# Sheet2.net
KiCad netlist of a schematic drawn in Altium Designer
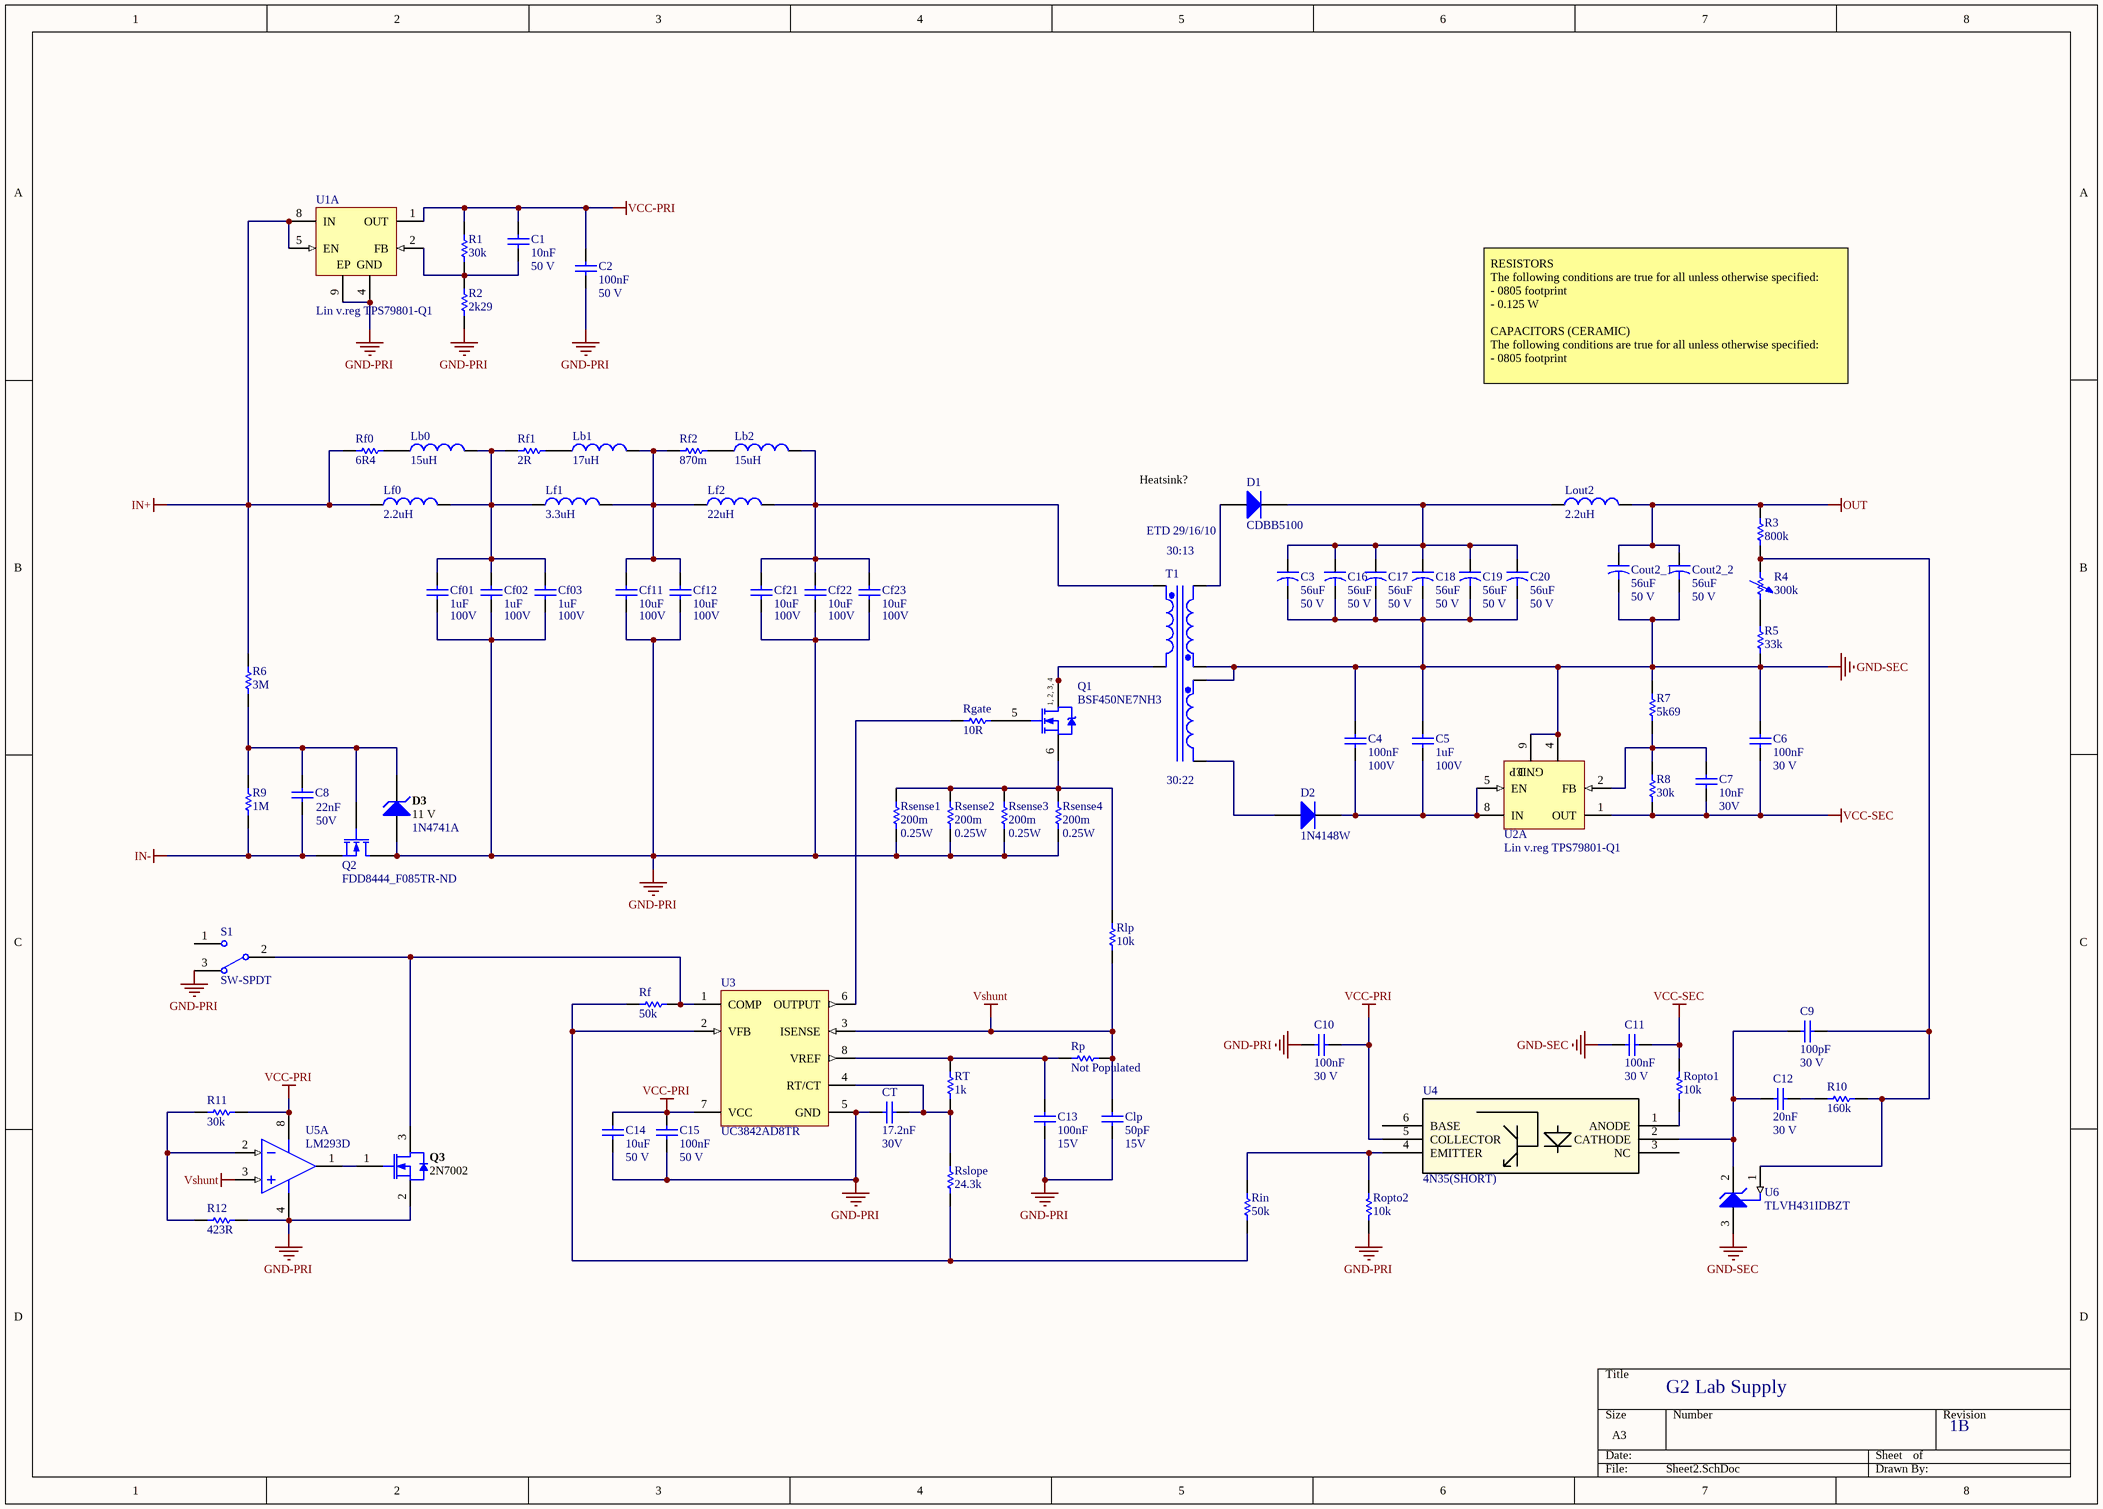
[diagram p0: Sheet2.SchDoc]

(export (version "E")
  (design (tool "Eeschema 10.0.6"))
  (components
    (comp (ref "C1")
      (value "10nF")
      (footprint "CAPC0805(2012)145_N")
      (description "CAP 82nF")
      (fields (field (name "RATED VOLTAGE") "50 V") (field (name "TOLERANCE") "Â±10%"))
      (libsource (lib "Altium Content Vault") (part "CMP-1036-04379-1"))
    )
    (comp (ref "C2")
      (value "100nF")
      (footprint "CAPC0805(2012)145_N")
      (description "CAP 82nF")
      (fields (field (name "RATED VOLTAGE") "50 V") (field (name "TOLERANCE") "Â±10%"))
      (libsource (lib "Altium Content Vault") (part "CMP-1036-04379-1"))
    )
    (comp (ref "C3")
      (value "56uF")
      (footprint "CAPR5-4X5")
      (description "Capacitor")
      (fields
        (field (name "VOLTAGE - RATED") "50 V")
        (field (name "Comment") "Cap2")
        (field (name "PUBLISHER") "Altium Limited")
      )
      (libsource (lib "Miscellaneous Devices") (part "Cap2"))
    )
    (comp (ref "C4")
      (value "100nF")
      (footprint "CAPC0805(2012)145_N")
      (description "footprint not correct")
      (fields (field (name "RATED VOLTAGE") "100V") (field (name "TOLERANCE") "Â±10%"))
      (libsource (lib "Altium Content Vault") (part "CMP-1036-04379-1"))
    )
    (comp (ref "C5")
      (value "1uF")
      (footprint "CAPC3216X180X20LL20")
      (description "Chip Capacitor, 1 uF, +/- 10%, 100 V, -55 to 125 degC, 1206 (3216 Metric), RoHS, Tape and Reel")
      (fields
        (field (name "MANUFACTURER") "TDK")
        (field (name "VOLTAGE - RATED") "100V")
        (field (name "TOLERANCE") "±10%")
      )
      (libsource (lib "Altium Content Vault") (part "CMP-2000-06049-1"))
    )
    (comp (ref "C6")
      (value "100nF")
      (footprint "CAPC0805(2012)145_N")
      (description "CAP 82nF")
      (fields (field (name "RATED VOLTAGE") "30 V") (field (name "TOLERANCE") "Â±10%"))
      (libsource (lib "Altium Content Vault") (part "CMP-1036-04379-1"))
    )
    (comp (ref "C7")
      (value "10nF")
      (footprint "CAPC0805(2012)145_N")
      (description "CAP 82nF")
      (fields (field (name "RATED VOLTAGE") "30V") (field (name "TOLERANCE") "Â±10%"))
      (libsource (lib "Altium Content Vault") (part "CMP-1036-04379-1"))
    )
    (comp (ref "C8")
      (value "22nF")
      (footprint "CAPC0805(2012)145_N")
      (description "CAP 82nF")
      (fields (field (name "RATED VOLTAGE") "50V") (field (name "TOLERANCE") "Â±10%"))
      (libsource (lib "Altium Content Vault") (part "CMP-1036-04379-1"))
    )
    (comp (ref "C9")
      (value "100pF")
      (footprint "CAPC0805(2012)145_N")
      (description "CAP 82nF")
      (fields (field (name "RATED VOLTAGE") "30 V") (field (name "TOLERANCE") "Â±10%"))
      (libsource (lib "Altium Content Vault") (part "CMP-1036-04379-1"))
    )
    (comp (ref "C10")
      (value "100nF")
      (footprint "CAPC0805(2012)145_N")
      (description "CAP 82nF")
      (fields (field (name "RATED VOLTAGE") "30 V") (field (name "TOLERANCE") "Â±10%"))
      (libsource (lib "Altium Content Vault") (part "CMP-1036-04379-1"))
    )
    (comp (ref "C11")
      (value "100nF")
      (footprint "CAPC0805(2012)145_N")
      (description "CAP 82nF")
      (fields (field (name "RATED VOLTAGE") "30 V") (field (name "TOLERANCE") "Â±10%"))
      (libsource (lib "Altium Content Vault") (part "CMP-1036-04379-1"))
    )
    (comp (ref "C12")
      (value "20nF")
      (footprint "CAPC0805(2012)145_N")
      (description "CAP 82nF")
      (fields (field (name "RATED VOLTAGE") "30 V") (field (name "TOLERANCE") "Â±10%"))
      (libsource (lib "Altium Content Vault") (part "CMP-1036-04379-1"))
    )
    (comp (ref "C13")
      (value "100nF")
      (footprint "CAPC0805(2012)145_N")
      (description "CAP 82nF")
      (fields (field (name "RATED VOLTAGE") "15V") (field (name "TOLERANCE") "Â±10%"))
      (libsource (lib "Altium Content Vault") (part "CMP-1036-04379-1"))
    )
    (comp (ref "C14")
      (value "10uF")
      (footprint "CAPC0805(2012)145_N")
      (description "CAP 82nF")
      (fields (field (name "RATED VOLTAGE") "50 V") (field (name "TOLERANCE") "Â±10%"))
      (libsource (lib "Altium Content Vault") (part "CMP-1036-04379-1"))
    )
    (comp (ref "C15")
      (value "100nF")
      (footprint "CAPC0805(2012)145_N")
      (description "CAP 82nF")
      (fields (field (name "RATED VOLTAGE") "50 V") (field (name "TOLERANCE") "Â±10%"))
      (libsource (lib "Altium Content Vault") (part "CMP-1036-04379-1"))
    )
    (comp (ref "C16")
      (value "56uF")
      (footprint "CAPR5-4X5")
      (description "Capacitor")
      (fields
        (field (name "VOLTAGE - RATED") "50 V")
        (field (name "Comment") "Cap2")
        (field (name "PUBLISHER") "Altium Limited")
      )
      (libsource (lib "Miscellaneous Devices") (part "Cap2"))
    )
    (comp (ref "C17")
      (value "56uF")
      (footprint "CAPR5-4X5")
      (description "Capacitor")
      (fields
        (field (name "VOLTAGE - RATED") "50 V")
        (field (name "Comment") "Cap2")
        (field (name "PUBLISHER") "Altium Limited")
      )
      (libsource (lib "Miscellaneous Devices") (part "Cap2"))
    )
    (comp (ref "C18")
      (value "56uF")
      (footprint "CAPR5-4X5")
      (description "Capacitor")
      (fields
        (field (name "VOLTAGE - RATED") "50 V")
        (field (name "Comment") "Cap2")
        (field (name "PUBLISHER") "Altium Limited")
      )
      (libsource (lib "Miscellaneous Devices") (part "Cap2"))
    )
    (comp (ref "C19")
      (value "56uF")
      (footprint "CAPR5-4X5")
      (description "Capacitor")
      (fields
        (field (name "VOLTAGE - RATED") "50 V")
        (field (name "Comment") "Cap2")
        (field (name "PUBLISHER") "Altium Limited")
      )
      (libsource (lib "Miscellaneous Devices") (part "Cap2"))
    )
    (comp (ref "C20")
      (value "56uF")
      (footprint "CAPR5-4X5")
      (description "Capacitor")
      (fields
        (field (name "VOLTAGE - RATED") "50 V")
        (field (name "Comment") "Cap2")
        (field (name "PUBLISHER") "Altium Limited")
      )
      (libsource (lib "Miscellaneous Devices") (part "Cap2"))
    )
    (comp (ref "Cf01")
      (value "1uF")
      (footprint "CAPC3216X180X20LL20")
      (description "Chip Capacitor, 1 uF, +/- 10%, 100 V, -55 to 125 degC, 1206 (3216 Metric), RoHS, Tape and Reel")
      (fields
        (field (name "MANUFACTURER") "TDK")
        (field (name "VOLTAGE - RATED") "100V")
        (field (name "TOLERANCE") "±10%")
      )
      (libsource (lib "Altium Content Vault") (part "CMP-2000-06049-1"))
    )
    (comp (ref "Cf02")
      (value "1uF")
      (footprint "CAPC3216X180X20LL20")
      (description "Chip Capacitor, 1 uF, +/- 10%, 100 V, -55 to 125 degC, 1206 (3216 Metric), RoHS, Tape and Reel")
      (fields
        (field (name "MANUFACTURER") "TDK")
        (field (name "VOLTAGE - RATED") "100V")
        (field (name "TOLERANCE") "±10%")
      )
      (libsource (lib "Altium Content Vault") (part "CMP-2000-06049-1"))
    )
    (comp (ref "Cf03")
      (value "1uF")
      (footprint "CAPC3216X180X20LL20")
      (description "Chip Capacitor, 1 uF, +/- 10%, 100 V, -55 to 125 degC, 1206 (3216 Metric), RoHS, Tape and Reel")
      (fields
        (field (name "MANUFACTURER") "TDK")
        (field (name "VOLTAGE - RATED") "100V")
        (field (name "TOLERANCE") "±10%")
      )
      (libsource (lib "Altium Content Vault") (part "CMP-2000-06049-1"))
    )
    (comp (ref "Cf11")
      (value "10uF")
      (footprint "CAPC5750X250X20LL40")
      (description "Chip Capacitor, 10 uF, +/- 10%, 100 V, -55 to 125 degC, 2220 (5750 Metric), RoHS, Tape and Reel")
      (fields (field (name "MANUFACTURER") "TDK") (field (name "VOLTAGE - RATED") "100V"))
      (libsource (lib "Altium Content Vault") (part "CMP-2000-07445-1"))
    )
    (comp (ref "Cf12")
      (value "10uF")
      (footprint "CAPC5750X250X20LL40")
      (description "Chip Capacitor, 10 uF, +/- 10%, 100 V, -55 to 125 degC, 2220 (5750 Metric), RoHS, Tape and Reel")
      (fields (field (name "MANUFACTURER") "TDK") (field (name "VOLTAGE - RATED") "100V"))
      (libsource (lib "Altium Content Vault") (part "CMP-2000-07445-1"))
    )
    (comp (ref "Cf21")
      (value "10uF")
      (footprint "CAPC5750X250X20LL40")
      (description "Chip Capacitor, 10 uF, +/- 10%, 100 V, -55 to 125 degC, 2220 (5750 Metric), RoHS, Tape and Reel")
      (fields (field (name "MANUFACTURER") "TDK") (field (name "VOLTAGE - RATED") "100V"))
      (libsource (lib "Altium Content Vault") (part "CMP-2000-07445-1"))
    )
    (comp (ref "Cf22")
      (value "10uF")
      (footprint "CAPC5750X250X20LL40")
      (description "Chip Capacitor, 10 uF, +/- 10%, 100 V, -55 to 125 degC, 2220 (5750 Metric), RoHS, Tape and Reel")
      (fields (field (name "MANUFACTURER") "TDK") (field (name "VOLTAGE - RATED") "100V"))
      (libsource (lib "Altium Content Vault") (part "CMP-2000-07445-1"))
    )
    (comp (ref "Cf23")
      (value "10uF")
      (footprint "CAPC5750X250X20LL40")
      (description "Chip Capacitor, 10 uF, +/- 10%, 100 V, -55 to 125 degC, 2220 (5750 Metric), RoHS, Tape and Reel")
      (fields (field (name "MANUFACTURER") "TDK") (field (name "VOLTAGE - RATED") "100V"))
      (libsource (lib "Altium Content Vault") (part "CMP-2000-07445-1"))
    )
    (comp (ref "Clp")
      (value "50pF")
      (footprint "CAPC0805(2012)145_N")
      (description "CAP 82nF")
      (fields (field (name "RATED VOLTAGE") "15V") (field (name "TOLERANCE") "Â±10%"))
      (libsource (lib "Altium Content Vault") (part "CMP-1036-04379-1"))
    )
    (comp (ref "Cout2_1")
      (value "56uF")
      (footprint "CAPR5-4X5")
      (description "Capacitor")
      (fields
        (field (name "VOLTAGE - RATED") "50 V")
        (field (name "Comment") "Cap2")
        (field (name "PUBLISHER") "Altium Limited")
      )
      (libsource (lib "Miscellaneous Devices") (part "Cap2"))
    )
    (comp (ref "Cout2_2")
      (value "56uF")
      (footprint "CAPR5-4X5")
      (description "Capacitor")
      (fields (field (name "VOLTAGE - RATED") "50 V") (field (name "PUBLISHER") "Altium Limited"))
      (libsource (lib "Miscellaneous Devices") (part "Cap2"))
    )
    (comp (ref "CT")
      (value "17.2nF")
      (footprint "CAPC0805(2012)145_N")
      (description "CAP 82nF")
      (fields (field (name "RATED VOLTAGE") "30V") (field (name "TOLERANCE") "Â±10%"))
      (libsource (lib "Altium Content Vault") (part "CMP-1036-04379-1"))
    )
    (comp (ref "D1")
      (value "CDBB5100")
      (footprint "SMC")
      (description "Default Diode")
      (fields (field (name "PUBLISHER") "Altium Limited"))
      (libsource (lib "Miscellaneous Devices") (part "Diode"))
    )
    (comp (ref "D2")
      (value "1N4148W")
      (footprint "JSCJ-SOD-123-2_V")
      (description "Fast Switching Diode, 75 V, 150 mA, 2-Pin 2.7 x 1.6 x 1.25 mm SMD, Tape and Reel")
      (fields (field (name "MANUFACTURER") "Changjiang Electronics"))
      (libsource (lib "Altium Content Vault") (part "CMP-0914-00001-1"))
    )
    (comp (ref "D3")
      (value "11 V")
      (footprint "FAIR-DO-41-2_V")
      (description "Zener Diode, 11V, 1W, 5%, -65 to 200 degC, 2-Pin DO-41, Body 2.72 x 5.2 mm, RoHS")
      (fields
        (field (name "MANUFACTURER") "Fairchild Semiconductor")
        (field (name "PARTNUMBER") "1N4741A")
        (field (name "TOLERANCE") "5%")
      )
      (libsource (lib "Altium Content Vault") (part "CMP-0892-00002-1"))
    )
    (comp (ref "Lb0")
      (value "15uH")
      (description "Inductor")
      (fields (field (name "PUBLISHER") "Altium Limited"))
      (libsource (lib "Miscellaneous Devices") (part "Inductor"))
    )
    (comp (ref "Lb1")
      (value "17uH")
      (description "Inductor")
      (fields (field (name "PUBLISHER") "Altium Limited"))
      (libsource (lib "Miscellaneous Devices") (part "Inductor"))
    )
    (comp (ref "Lb2")
      (value "15uH")
      (description "Inductor")
      (fields (field (name "PUBLISHER") "Altium Limited"))
      (libsource (lib "Miscellaneous Devices") (part "Inductor"))
    )
    (comp (ref "Lf0")
      (value "2.2uH")
      (description "Inductor")
      (fields (field (name "PUBLISHER") "Altium Limited"))
      (libsource (lib "Miscellaneous Devices") (part "Inductor"))
    )
    (comp (ref "Lf1")
      (value "3.3uH")
      (description "Inductor")
      (fields (field (name "PUBLISHER") "Altium Limited"))
      (libsource (lib "Miscellaneous Devices") (part "Inductor"))
    )
    (comp (ref "Lf2")
      (value "22uH")
      (description "Inductor")
      (fields (field (name "PUBLISHER") "Altium Limited"))
      (libsource (lib "Miscellaneous Devices") (part "Inductor"))
    )
    (comp (ref "Lout2")
      (value "2.2uH")
      (description "Inductor")
      (fields (field (name "PUBLISHER") "Altium Limited"))
      (libsource (lib "Miscellaneous Devices") (part "Inductor"))
    )
    (comp (ref "Q1")
      (value "BSF450NE7NH3")
      (footprint "INF-MG-WDSON-2-1_V")
      (description "N-Channel OptiMOS 3 Power-MOSFET, 75 V VDS, 15 A ID, -40 to 150 degC, MG-WDSON-2-1, Reel, Green")
      (fields (field (name "MANUFACTURER") "Infineon"))
      (libsource (lib "Altium Content Vault") (part "CMP-1091-00001-1"))
    )
    (comp (ref "Q2")
      (value "FDD8444_F085TR-ND")
      (fields (field (name "PUBLISHER") "Altium Limited"))
      (libsource (lib "Miscellaneous Devices") (part "MOSFET-N"))
    )
    (comp (ref "Q3")
      (value "2N7002")
      (footprint "INF-PG-SOT23_M")
      (fields (field (name "MANUFACTURER") "Infineon"))
      (libsource (lib "Altium Content Vault") (part "INF-NDMOS-GSD-3"))
    )
    (comp (ref "R1")
      (value "30k")
      (footprint "RESC0805(2012)_L")
      (fields (field (name "TOLERANCE") "1 %") (field (name "POWER") "0.125 W"))
      (libsource (lib "Altium Content Vault") (part "CMP-1013-00736-1"))
    )
    (comp (ref "R2")
      (value "2k29")
      (footprint "RESC0805(2012)_L")
      (fields (field (name "TOLERANCE") "1 %") (field (name "POWER") "0.125 W"))
      (libsource (lib "Altium Content Vault") (part "CMP-1013-00736-1"))
    )
    (comp (ref "R3")
      (value "800k")
      (footprint "RESC0805(2012)_L")
      (fields (field (name "TOLERANCE") "1 %") (field (name "POWER") "0.125 W"))
      (libsource (lib "Altium Content Vault") (part "CMP-1013-00736-1"))
    )
    (comp (ref "R4")
      (value "300k")
      (footprint "AXIAL-0.7")
      (description "Variable Resistor")
      (fields (field (name "PUBLISHER") "Altium Limited"))
      (libsource (lib "Miscellaneous Devices") (part "Res Adj1"))
    )
    (comp (ref "R5")
      (value "33k")
      (footprint "RESC0805(2012)_L")
      (fields (field (name "TOLERANCE") "1 %") (field (name "POWER") "0.125 W"))
      (libsource (lib "Altium Content Vault") (part "CMP-1013-00736-1"))
    )
    (comp (ref "R6")
      (value "3M")
      (footprint "RESC0805(2012)_L")
      (fields (field (name "TOLERANCE") "1 %") (field (name "POWER") "0.125 W"))
      (libsource (lib "Altium Content Vault") (part "CMP-1013-00736-1"))
    )
    (comp (ref "R7")
      (value "5k69")
      (footprint "RESC0805(2012)_L")
      (fields (field (name "TOLERANCE") "1 %") (field (name "POWER") "0.125 W"))
      (libsource (lib "Altium Content Vault") (part "CMP-1013-00736-1"))
    )
    (comp (ref "R8")
      (value "30k")
      (footprint "RESC0805(2012)_L")
      (fields (field (name "TOLERANCE") "1 %") (field (name "POWER") "0.125 W"))
      (libsource (lib "Altium Content Vault") (part "CMP-1013-00736-1"))
    )
    (comp (ref "R9")
      (value "1M")
      (footprint "RESC0805(2012)_L")
      (fields (field (name "TOLERANCE") "1 %") (field (name "POWER") "0.125 W"))
      (libsource (lib "Altium Content Vault") (part "CMP-1013-00736-1"))
    )
    (comp (ref "R10")
      (value "160k")
      (footprint "RESC0805(2012)_L")
      (fields (field (name "TOLERANCE") "1 %") (field (name "POWER") "0.125 W"))
      (libsource (lib "Altium Content Vault") (part "CMP-1013-00736-1"))
    )
    (comp (ref "R11")
      (value "30k")
      (footprint "RESC0805(2012)_L")
      (fields (field (name "TOLERANCE") "1 %") (field (name "POWER") "0.125 W"))
      (libsource (lib "Altium Content Vault") (part "CMP-1013-00736-1"))
    )
    (comp (ref "R12")
      (value "423R")
      (footprint "RESC0805(2012)_L")
      (fields (field (name "TOLERANCE") "1 %") (field (name "POWER") "0.125 W"))
      (libsource (lib "Altium Content Vault") (part "CMP-1013-00736-1"))
    )
    (comp (ref "Rf")
      (value "50k")
      (footprint "RESC0805(2012)_L")
      (fields (field (name "TOLERANCE") "1 %") (field (name "POWER") "0.125 W"))
      (libsource (lib "Altium Content Vault") (part "CMP-1013-00736-1"))
    )
    (comp (ref "Rf0")
      (value "6R4")
      (footprint "RESC0805(2012)_L")
      (fields (field (name "TOLERANCE") "1 %") (field (name "POWER") "0.125 W"))
      (libsource (lib "Altium Content Vault") (part "CMP-1013-00736-1"))
    )
    (comp (ref "Rf1")
      (value "2R")
      (footprint "RESC0805(2012)_L")
      (fields (field (name "TOLERANCE") "1 %") (field (name "POWER") "0.125 W"))
      (libsource (lib "Altium Content Vault") (part "CMP-1013-00736-1"))
    )
    (comp (ref "Rf2")
      (value "870m")
      (footprint "RESC0805(2012)_L")
      (fields (field (name "TOLERANCE") "1 %") (field (name "POWER") "0.125 W"))
      (libsource (lib "Altium Content Vault") (part "CMP-1013-00736-1"))
    )
    (comp (ref "Rgate")
      (value "10R")
      (footprint "RESC0805(2012)_L")
      (fields (field (name "TOLERANCE") "1 %") (field (name "POWER") "0.125 W"))
      (libsource (lib "Altium Content Vault") (part "CMP-1013-00736-1"))
    )
    (comp (ref "Rin")
      (value "50k")
      (footprint "RESC0805(2012)_L")
      (fields (field (name "TOLERANCE") "1 %") (field (name "POWER") "0.125 W"))
      (libsource (lib "Altium Content Vault") (part "CMP-1013-00736-1"))
    )
    (comp (ref "Rlp")
      (value "10k")
      (footprint "RESC0805(2012)_L")
      (fields (field (name "TOLERANCE") "1 %") (field (name "POWER") "0.125 W"))
      (libsource (lib "Altium Content Vault") (part "CMP-1013-00736-1"))
    )
    (comp (ref "Ropto1")
      (value "10k")
      (footprint "RESC0805(2012)_L")
      (fields (field (name "TOLERANCE") "1 %") (field (name "POWER") "0.125 W"))
      (libsource (lib "Altium Content Vault") (part "CMP-1013-00736-1"))
    )
    (comp (ref "Ropto2")
      (value "10k")
      (footprint "RESC0805(2012)_L")
      (fields (field (name "TOLERANCE") "1 %") (field (name "POWER") "0.125 W"))
      (libsource (lib "Altium Content Vault") (part "CMP-1013-00736-1"))
    )
    (comp (ref "Rp")
      (value "Not Populated")
      (footprint "RESC0805(2012)_L")
      (description "Biasing current sense")
      (fields (field (name "TOLERANCE") "1 %") (field (name "POWER") "0.125 W"))
      (libsource (lib "Altium Content Vault") (part "CMP-1013-00736-1"))
    )
    (comp (ref "Rsense1")
      (value "200m")
      (footprint "RESC0805(2012)_L")
      (description "wrong footprint")
      (fields (field (name "TOLERANCE") "1 %") (field (name "POWER") "0.25W"))
      (libsource (lib "Altium Content Vault") (part "CMP-1013-00736-1"))
    )
    (comp (ref "Rsense2")
      (value "200m")
      (footprint "RESC0805(2012)_L")
      (description "wrong footprint")
      (fields (field (name "TOLERANCE") "1 %") (field (name "POWER") "0.25W"))
      (libsource (lib "Altium Content Vault") (part "CMP-1013-00736-1"))
    )
    (comp (ref "Rsense3")
      (value "200m")
      (footprint "RESC0805(2012)_L")
      (description "wrong footprint")
      (fields (field (name "TOLERANCE") "1 %") (field (name "POWER") "0.25W"))
      (libsource (lib "Altium Content Vault") (part "CMP-1013-00736-1"))
    )
    (comp (ref "Rsense4")
      (value "200m")
      (footprint "RESC0805(2012)_L")
      (description "wrong footprint")
      (fields (field (name "TOLERANCE") "1 %") (field (name "POWER") "0.25W"))
      (libsource (lib "Altium Content Vault") (part "CMP-1013-00736-1"))
    )
    (comp (ref "Rslope")
      (value "24.3k")
      (footprint "RESC0805(2012)_L")
      (fields (field (name "TOLERANCE") "1 %") (field (name "POWER") "0.125 W"))
      (libsource (lib "Altium Content Vault") (part "CMP-1013-00736-1"))
    )
    (comp (ref "RT")
      (value "1k")
      (footprint "RESC0805(2012)_L")
      (fields (field (name "TOLERANCE") "1 %") (field (name "POWER") "0.125 W"))
      (libsource (lib "Altium Content Vault") (part "CMP-1013-00736-1"))
    )
    (comp (ref "S1")
      (value "SW-SPDT")
      (footprint "TL36WW15050")
      (description "SPDT Subminiature Toggle Switch, Right Angle Mounting, Vertical Actuation")
      (fields (field (name "PUBLISHER") "Altium Limited"))
      (libsource (lib "Miscellaneous Devices") (part "SW-SPDT"))
    )
    (comp (ref "T1")
      (value "ETD 29/16/10, Turns ratio 30:13:22")
      (footprint "ETD 29/16/10 v2")
      (description "Three-winding Transformer (Non-Ideal)")
      (libsource (lib "Flyback") (part "Trans3"))
    )
    (comp (ref "U1")
      (value "Lin v.reg TPS79801-Q1")
      (footprint "DGN0008B_N")
      (description "got this footprint from a similar model")
      (fields (field (name "MANUFACTURER") "Texas Instruments") (field (name "PARTNUMBER") "TPS79801QDGNRQ1"))
      (libsource (lib "Altium Content Vault") (part "CMP-0394-01260-2"))
    )
    (comp (ref "U2")
      (value "Lin v.reg TPS79801-Q1")
      (footprint "DGN0008B_N")
      (description "got this footprint from a similar model")
      (fields (field (name "MANUFACTURER") "Texas Instruments") (field (name "PARTNUMBER") "TPS79801QDGNRQ1"))
      (libsource (lib "") (part "CMP-0394-01260-2_1"))
    )
    (comp (ref "U3")
      (value "UC3842AD8TR")
      (footprint "D0008A_L")
      (fields (field (name "MANUFACTURER") "Texas Instruments"))
      (libsource (lib "Altium Content Vault") (part "TI-UC3842AD8"))
    )
    (comp (ref "U4")
      (value "4N35(SHORT)")
      (footprint "4N35")
      (description "Imported")
      (libsource (lib "AltiumDesigner") (part "4N35(SHORT)"))
    )
    (comp (ref "U5")
      (value "LM293D")
      (footprint "D0008A_M")
      (fields (field (name "MANUFACTURER") "Texas Instruments"))
      (libsource (lib "Altium Content Vault") (part "TI-LMX93X-8"))
    )
    (comp (ref "U6")
      (value "TLVH431IDBZT")
      (footprint "TI-DBZ3_N")
      (fields (field (name "MANUFACTURER") "Texas Instruments"))
      (libsource (lib "Altium Content Vault") (part "TI-TLVH431DBZ3"))
    )
  )
  (nets
    (net (code "1") (name "GND-PRI") (class "Default")
      (node (ref "C10") (pin "1") (pinfunction "1_1") (pintype "passive"))
      (node (ref "C13") (pin "2") (pinfunction "2_2") (pintype "passive"))
      (node (ref "C14") (pin "1") (pinfunction "1_1") (pintype "passive"))
      (node (ref "C15") (pin "1") (pinfunction "1_1") (pintype "passive"))
      (node (ref "C2") (pin "1") (pinfunction "1_1") (pintype "passive"))
      (node (ref "CT") (pin "2") (pinfunction "2_2") (pintype "passive"))
      (node (ref "Cf01") (pin "1") (pinfunction "1_1") (pintype "passive"))
      (node (ref "Cf02") (pin "1") (pinfunction "1_1") (pintype "passive"))
      (node (ref "Cf03") (pin "1") (pinfunction "1_1") (pintype "passive"))
      (node (ref "Cf11") (pin "1") (pinfunction "1_1") (pintype "passive"))
      (node (ref "Cf12") (pin "1") (pinfunction "1_1") (pintype "passive"))
      (node (ref "Cf21") (pin "1") (pinfunction "1_1") (pintype "passive"))
      (node (ref "Cf22") (pin "1") (pinfunction "1_1") (pintype "passive"))
      (node (ref "Cf23") (pin "1") (pinfunction "1_1") (pintype "passive"))
      (node (ref "Clp") (pin "1") (pinfunction "1_1") (pintype "passive"))
      (node (ref "D3") (pin "1") (pinfunction "A_1") (pintype "passive"))
      (node (ref "Q2") (pin "1") (pinfunction "D_1") (pintype "passive"))
      (node (ref "Q3") (pin "2") (pinfunction "SOURCE_2") (pintype "passive"))
      (node (ref "R12") (pin "2") (pinfunction "2_2") (pintype "passive"))
      (node (ref "R2") (pin "1") (pinfunction "1_1") (pintype "passive"))
      (node (ref "Ropto2") (pin "1") (pinfunction "1_1") (pintype "passive"))
      (node (ref "Rsense1") (pin "1") (pinfunction "1_1") (pintype "passive"))
      (node (ref "Rsense2") (pin "1") (pinfunction "1_1") (pintype "passive"))
      (node (ref "Rsense3") (pin "1") (pinfunction "1_1") (pintype "passive"))
      (node (ref "Rsense4") (pin "1") (pinfunction "1_1") (pintype "passive"))
      (node (ref "S1") (pin "3") (pinfunction "3_3") (pintype "passive"))
      (node (ref "U1") (pin "4") (pinfunction "GND_4") (pintype "power_in"))
      (node (ref "U1") (pin "9") (pinfunction "EP_9") (pintype "power_in"))
      (node (ref "U3") (pin "5") (pinfunction "GND_5") (pintype "power_in"))
      (node (ref "U5") (pin "4") (pinfunction "GND_4") (pintype "power_in"))
    )
    (net (code "2") (name "GND-SEC") (class "Default")
      (node (ref "C11") (pin "1") (pinfunction "1_1") (pintype "passive"))
      (node (ref "C16") (pin "2") (pinfunction "2_2") (pintype "passive"))
      (node (ref "C17") (pin "2") (pinfunction "2_2") (pintype "passive"))
      (node (ref "C18") (pin "2") (pinfunction "2_2") (pintype "passive"))
      (node (ref "C19") (pin "2") (pinfunction "2_2") (pintype "passive"))
      (node (ref "C20") (pin "2") (pinfunction "2_2") (pintype "passive"))
      (node (ref "C3") (pin "2") (pinfunction "2_2") (pintype "passive"))
      (node (ref "C4") (pin "2") (pinfunction "2_2") (pintype "passive"))
      (node (ref "C5") (pin "2") (pinfunction "2_2") (pintype "passive"))
      (node (ref "C6") (pin "2") (pinfunction "2_2") (pintype "passive"))
      (node (ref "Cout2_1") (pin "2") (pinfunction "2_2") (pintype "passive"))
      (node (ref "Cout2_2") (pin "2") (pinfunction "2_2") (pintype "passive"))
      (node (ref "R5") (pin "1") (pinfunction "1_1") (pintype "passive"))
      (node (ref "R7") (pin "1") (pinfunction "1_1") (pintype "passive"))
      (node (ref "T1") (pin "3") (pinfunction "Sec1+_3") (pintype "passive"))
      (node (ref "T1") (pin "5") (pinfunction "Sec2+_5") (pintype "passive"))
      (node (ref "U2") (pin "4") (pinfunction "GND_4") (pintype "power_in"))
      (node (ref "U2") (pin "9") (pinfunction "EP_9") (pintype "power_in"))
      (node (ref "U6") (pin "3") (pinfunction "ANODE_3") (pintype "passive"))
    )
    (net (code "3") (name "IN+") (class "Default")
      (node (ref "Lf0") (pin "1") (pinfunction "1_1") (pintype "passive"))
      (node (ref "R6") (pin "2") (pinfunction "2_2") (pintype "passive"))
      (node (ref "Rf0") (pin "2") (pinfunction "2_2") (pintype "passive"))
      (node (ref "U1") (pin "5") (pinfunction "EN_5") (pintype "input"))
      (node (ref "U1") (pin "8") (pinfunction "IN_8") (pintype "power_in"))
    )
    (net (code "4") (name "IN-") (class "Default")
      (node (ref "C8") (pin "1") (pinfunction "1_1") (pintype "passive"))
      (node (ref "Q2") (pin "3") (pinfunction "S_3") (pintype "passive"))
      (node (ref "R9") (pin "1") (pinfunction "1_1") (pintype "passive"))
    )
    (net (code "5") (name "Net-(C12-Pad2)") (class "Default")
      (node (ref "C12") (pin "2") (pinfunction "2_2") (pintype "passive"))
      (node (ref "R10") (pin "2") (pinfunction "2_2") (pintype "passive"))
    )
    (net (code "6") (name "Net-(Cf01-Pad2)") (class "Default")
      (node (ref "Cf01") (pin "2") (pinfunction "2_2") (pintype "passive"))
      (node (ref "Cf02") (pin "2") (pinfunction "2_2") (pintype "passive"))
      (node (ref "Cf03") (pin "2") (pinfunction "2_2") (pintype "passive"))
      (node (ref "Lb0") (pin "2") (pinfunction "2_2") (pintype "passive"))
      (node (ref "Lf0") (pin "2") (pinfunction "2_2") (pintype "passive"))
      (node (ref "Lf1") (pin "1") (pinfunction "1_1") (pintype "passive"))
      (node (ref "Rf1") (pin "2") (pinfunction "2_2") (pintype "passive"))
    )
    (net (code "7") (name "Net-(Cf11-Pad2)") (class "Default")
      (node (ref "Cf11") (pin "2") (pinfunction "2_2") (pintype "passive"))
      (node (ref "Cf12") (pin "2") (pinfunction "2_2") (pintype "passive"))
      (node (ref "Lb1") (pin "2") (pinfunction "2_2") (pintype "passive"))
      (node (ref "Lf1") (pin "2") (pinfunction "2_2") (pintype "passive"))
      (node (ref "Lf2") (pin "1") (pinfunction "1_1") (pintype "passive"))
      (node (ref "Rf2") (pin "2") (pinfunction "2_2") (pintype "passive"))
    )
    (net (code "8") (name "Net-(D1-A)") (class "Default")
      (node (ref "D1") (pin "1") (pinfunction "A_1") (pintype "passive"))
      (node (ref "T1") (pin "4") (pinfunction "Sec1-_4") (pintype "passive"))
    )
    (net (code "9") (name "Net-(D1-K)") (class "Default")
      (node (ref "C16") (pin "1") (pinfunction "1_1") (pintype "passive"))
      (node (ref "C17") (pin "1") (pinfunction "1_1") (pintype "passive"))
      (node (ref "C18") (pin "1") (pinfunction "1_1") (pintype "passive"))
      (node (ref "C19") (pin "1") (pinfunction "1_1") (pintype "passive"))
      (node (ref "C20") (pin "1") (pinfunction "1_1") (pintype "passive"))
      (node (ref "C3") (pin "1") (pinfunction "1_1") (pintype "passive"))
      (node (ref "D1") (pin "2") (pinfunction "K_2") (pintype "passive"))
      (node (ref "Lout2") (pin "1") (pinfunction "1_1") (pintype "passive"))
    )
    (net (code "10") (name "Net-(D2-+)") (class "Default")
      (node (ref "D2") (pin "1") (pinfunction "+_1") (pintype "passive"))
      (node (ref "T1") (pin "6") (pinfunction "Sec2-_6") (pintype "passive"))
    )
    (net (code "11") (name "Net-(D2--)") (class "Default")
      (node (ref "C4") (pin "1") (pinfunction "1_1") (pintype "passive"))
      (node (ref "C5") (pin "1") (pinfunction "1_1") (pintype "passive"))
      (node (ref "D2") (pin "2") (pinfunction "-_2") (pintype "passive"))
      (node (ref "U2") (pin "5") (pinfunction "EN_5") (pintype "input"))
      (node (ref "U2") (pin "8") (pinfunction "IN_8") (pintype "power_in"))
    )
    (net (code "12") (name "Net-(D3-K)") (class "Default")
      (node (ref "C8") (pin "2") (pinfunction "2_2") (pintype "passive"))
      (node (ref "D3") (pin "2") (pinfunction "K_2") (pintype "passive"))
      (node (ref "Q2") (pin "2") (pinfunction "G_2") (pintype "passive"))
      (node (ref "R6") (pin "1") (pinfunction "1_1") (pintype "passive"))
      (node (ref "R9") (pin "2") (pinfunction "2_2") (pintype "passive"))
    )
    (net (code "13") (name "Net-(Lb0-Pad1)") (class "Default")
      (node (ref "Lb0") (pin "1") (pinfunction "1_1") (pintype "passive"))
      (node (ref "Rf0") (pin "1") (pinfunction "1_1") (pintype "passive"))
    )
    (net (code "14") (name "Net-(Lb1-Pad1)") (class "Default")
      (node (ref "Lb1") (pin "1") (pinfunction "1_1") (pintype "passive"))
      (node (ref "Rf1") (pin "1") (pinfunction "1_1") (pintype "passive"))
    )
    (net (code "15") (name "Net-(Lb2-Pad1)") (class "Default")
      (node (ref "Lb2") (pin "1") (pinfunction "1_1") (pintype "passive"))
      (node (ref "Rf2") (pin "1") (pinfunction "1_1") (pintype "passive"))
    )
    (net (code "16") (name "Net-(Q1-GATE)") (class "Default")
      (node (ref "Q1") (pin "5") (pinfunction "GATE_5") (pintype "passive"))
      (node (ref "Rgate") (pin "1") (pinfunction "1_1") (pintype "passive"))
    )
    (net (code "17") (name "Net-(Q1-SOURCE)") (class "Default")
      (node (ref "Q1") (pin "6") (pinfunction "SOURCE_6") (pintype "passive"))
      (node (ref "Rlp") (pin "1") (pinfunction "1_1") (pintype "passive"))
      (node (ref "Rsense1") (pin "2") (pinfunction "2_2") (pintype "passive"))
      (node (ref "Rsense2") (pin "2") (pinfunction "2_2") (pintype "passive"))
      (node (ref "Rsense3") (pin "2") (pinfunction "2_2") (pintype "passive"))
      (node (ref "Rsense4") (pin "2") (pinfunction "2_2") (pintype "passive"))
    )
    (net (code "18") (name "Net-(Q3-DRAIN)") (class "Default")
      (node (ref "Q3") (pin "3") (pinfunction "DRAIN_3") (pintype "passive"))
      (node (ref "Rf") (pin "1") (pinfunction "1_1") (pintype "passive"))
      (node (ref "S1") (pin "2") (pinfunction "2_2") (pintype "passive"))
      (node (ref "U3") (pin "1") (pinfunction "COMP_1") (pintype "passive"))
    )
    (net (code "19") (name "Net-(Q3-GATE)") (class "Default")
      (node (ref "Q3") (pin "1") (pinfunction "GATE_1") (pintype "passive"))
      (node (ref "U5") (pin "1") (pinfunction "OUT1_1") (pintype "tri_state"))
    )
    (net (code "20") (name "Net-(R4-Pad2)") (class "Default")
      (node (ref "R4") (pin "2") (pinfunction "2_2") (pintype "passive"))
      (node (ref "R5") (pin "2") (pinfunction "2_2") (pintype "passive"))
    )
    (net (code "21") (name "Net-(T1-Pri+)") (class "Default")
      (node (ref "Cf21") (pin "2") (pinfunction "2_2") (pintype "passive"))
      (node (ref "Cf22") (pin "2") (pinfunction "2_2") (pintype "passive"))
      (node (ref "Cf23") (pin "2") (pinfunction "2_2") (pintype "passive"))
      (node (ref "Lb2") (pin "2") (pinfunction "2_2") (pintype "passive"))
      (node (ref "Lf2") (pin "2") (pinfunction "2_2") (pintype "passive"))
      (node (ref "T1") (pin "1") (pinfunction "Pri+_1") (pintype "passive"))
    )
    (net (code "22") (name "Net-(T1-Pri-)") (class "Default")
      (node (ref "Q1") (pin "1") (pinfunction "DRAIN_1") (pintype "passive"))
      (node (ref "Q1") (pin "2") (pinfunction "DRAIN_2") (pintype "passive"))
      (node (ref "Q1") (pin "3") (pinfunction "DRAIN_3") (pintype "passive"))
      (node (ref "Q1") (pin "4") (pinfunction "DRAIN_4") (pintype "passive"))
      (node (ref "T1") (pin "2") (pinfunction "Pri-_2") (pintype "passive"))
    )
    (net (code "23") (name "Net-(U1A-FB)") (class "Default")
      (node (ref "C1") (pin "1") (pinfunction "1_1") (pintype "passive"))
      (node (ref "R1") (pin "1") (pinfunction "1_1") (pintype "passive"))
      (node (ref "R2") (pin "2") (pinfunction "2_2") (pintype "passive"))
      (node (ref "U1") (pin "2") (pinfunction "FB_2") (pintype "input"))
    )
    (net (code "24") (name "Net-(U2A-FB)") (class "Default")
      (node (ref "C7") (pin "2") (pinfunction "2_2") (pintype "passive"))
      (node (ref "R7") (pin "2") (pinfunction "2_2") (pintype "passive"))
      (node (ref "R8") (pin "1") (pinfunction "1_1") (pintype "passive"))
      (node (ref "U2") (pin "2") (pinfunction "FB_2") (pintype "input"))
    )
    (net (code "25") (name "Net-(U3-OUTPUT)") (class "Default")
      (node (ref "Rgate") (pin "2") (pinfunction "2_2") (pintype "passive"))
      (node (ref "U3") (pin "6") (pinfunction "OUTPUT_6") (pintype "output"))
    )
    (net (code "26") (name "Net-(U3-RT{slash}CT)") (class "Default")
      (node (ref "CT") (pin "1") (pinfunction "1_1") (pintype "passive"))
      (node (ref "RT") (pin "1") (pinfunction "1_1") (pintype "passive"))
      (node (ref "Rslope") (pin "1") (pinfunction "1_1") (pintype "passive"))
      (node (ref "U3") (pin "4") (pinfunction "RT/CT_4") (pintype "passive"))
    )
    (net (code "27") (name "Net-(U3-VFB)") (class "Default")
      (node (ref "Rf") (pin "2") (pinfunction "2_2") (pintype "passive"))
      (node (ref "Rin") (pin "2") (pinfunction "2_2") (pintype "passive"))
      (node (ref "Rslope") (pin "2") (pinfunction "2_2") (pintype "passive"))
      (node (ref "U3") (pin "2") (pinfunction "VFB_2") (pintype "input"))
    )
    (net (code "28") (name "Net-(U3-VREF)") (class "Default")
      (node (ref "C13") (pin "1") (pinfunction "1_1") (pintype "passive"))
      (node (ref "RT") (pin "2") (pinfunction "2_2") (pintype "passive"))
      (node (ref "Rp") (pin "1") (pinfunction "1_1") (pintype "passive"))
      (node (ref "U3") (pin "8") (pinfunction "VREF_8") (pintype "output"))
    )
    (net (code "29") (name "Net-(U4-ANODE)") (class "Default")
      (node (ref "Ropto1") (pin "2") (pinfunction "2_2") (pintype "passive"))
      (node (ref "U4") (pin "1") (pinfunction "ANODE_1") (pintype "passive"))
    )
    (net (code "30") (name "Net-(U4-CATHODE)") (class "Default")
      (node (ref "C12") (pin "1") (pinfunction "1_1") (pintype "passive"))
      (node (ref "C9") (pin "1") (pinfunction "1_1") (pintype "passive"))
      (node (ref "U4") (pin "2") (pinfunction "CATHODE_2") (pintype "passive"))
      (node (ref "U6") (pin "2") (pinfunction "CATHODE_2") (pintype "passive"))
    )
    (net (code "31") (name "Net-(U4-EMITTER)") (class "Default")
      (node (ref "Rin") (pin "1") (pinfunction "1_1") (pintype "passive"))
      (node (ref "Ropto2") (pin "2") (pinfunction "2_2") (pintype "passive"))
      (node (ref "U4") (pin "4") (pinfunction "EMITTER_4") (pintype "passive"))
    )
    (net (code "32") (name "Net-(U5A-IN1-)") (class "Default")
      (node (ref "R11") (pin "1") (pinfunction "1_1") (pintype "passive"))
      (node (ref "R12") (pin "1") (pinfunction "1_1") (pintype "passive"))
      (node (ref "U5") (pin "2") (pinfunction "IN1-_2") (pintype "input"))
    )
    (net (code "33") (name "Net-(U6-REF)") (class "Default")
      (node (ref "C9") (pin "2") (pinfunction "2_2") (pintype "passive"))
      (node (ref "R10") (pin "1") (pinfunction "1_1") (pintype "passive"))
      (node (ref "R3") (pin "1") (pinfunction "1_1") (pintype "passive"))
      (node (ref "R4") (pin "1") (pinfunction "1_1") (pintype "passive"))
      (node (ref "U6") (pin "1") (pinfunction "REF_1") (pintype "input"))
    )
    (net (code "34") (name "OUT") (class "Default")
      (node (ref "Cout2_1") (pin "1") (pinfunction "1_1") (pintype "passive"))
      (node (ref "Cout2_2") (pin "1") (pinfunction "1_1") (pintype "passive"))
      (node (ref "Lout2") (pin "2") (pinfunction "2_2") (pintype "passive"))
      (node (ref "R3") (pin "2") (pinfunction "2_2") (pintype "passive"))
    )
    (net (code "35") (name "VCC-PRI") (class "Default")
      (node (ref "C1") (pin "2") (pinfunction "2_2") (pintype "passive"))
      (node (ref "C10") (pin "2") (pinfunction "2_2") (pintype "passive"))
      (node (ref "C14") (pin "2") (pinfunction "2_2") (pintype "passive"))
      (node (ref "C15") (pin "2") (pinfunction "2_2") (pintype "passive"))
      (node (ref "C2") (pin "2") (pinfunction "2_2") (pintype "passive"))
      (node (ref "R1") (pin "2") (pinfunction "2_2") (pintype "passive"))
      (node (ref "R11") (pin "2") (pinfunction "2_2") (pintype "passive"))
      (node (ref "U1") (pin "1") (pinfunction "OUT_1") (pintype "power_in"))
      (node (ref "U3") (pin "7") (pinfunction "VCC_7") (pintype "power_in"))
      (node (ref "U4") (pin "5") (pinfunction "COLLECTOR_5") (pintype "passive"))
      (node (ref "U5") (pin "8") (pinfunction "VCC_8") (pintype "power_in"))
    )
    (net (code "36") (name "VCC-SEC") (class "Default")
      (node (ref "C11") (pin "2") (pinfunction "2_2") (pintype "passive"))
      (node (ref "C6") (pin "1") (pinfunction "1_1") (pintype "passive"))
      (node (ref "C7") (pin "1") (pinfunction "1_1") (pintype "passive"))
      (node (ref "R8") (pin "2") (pinfunction "2_2") (pintype "passive"))
      (node (ref "Ropto1") (pin "1") (pinfunction "1_1") (pintype "passive"))
      (node (ref "U2") (pin "1") (pinfunction "OUT_1") (pintype "power_in"))
    )
    (net (code "37") (name "Vshunt") (class "Default")
      (node (ref "Clp") (pin "2") (pinfunction "2_2") (pintype "passive"))
      (node (ref "Rlp") (pin "2") (pinfunction "2_2") (pintype "passive"))
      (node (ref "Rp") (pin "2") (pinfunction "2_2") (pintype "passive"))
      (node (ref "U3") (pin "3") (pinfunction "ISENSE_3") (pintype "input"))
      (node (ref "U5") (pin "3") (pinfunction "IN1+_3") (pintype "input"))
    )
    (net (code "38") (name "unconnected-(S1-Pad1)") (class "Default")
      (node (ref "S1") (pin "1") (pinfunction "1_1") (pintype "passive"))
    )
    (net (code "39") (name "unconnected-(U4-BASE-Pad6)") (class "Default")
      (node (ref "U4") (pin "6") (pinfunction "BASE_6") (pintype "passive"))
    )
    (net (code "40") (name "unconnected-(U4-NC-Pad3)") (class "Default")
      (node (ref "U4") (pin "3") (pinfunction "NC_3") (pintype "passive"))
    )
  )
)
